# 3333.net
KiCad netlist of a schematic drawn in Altium Designer
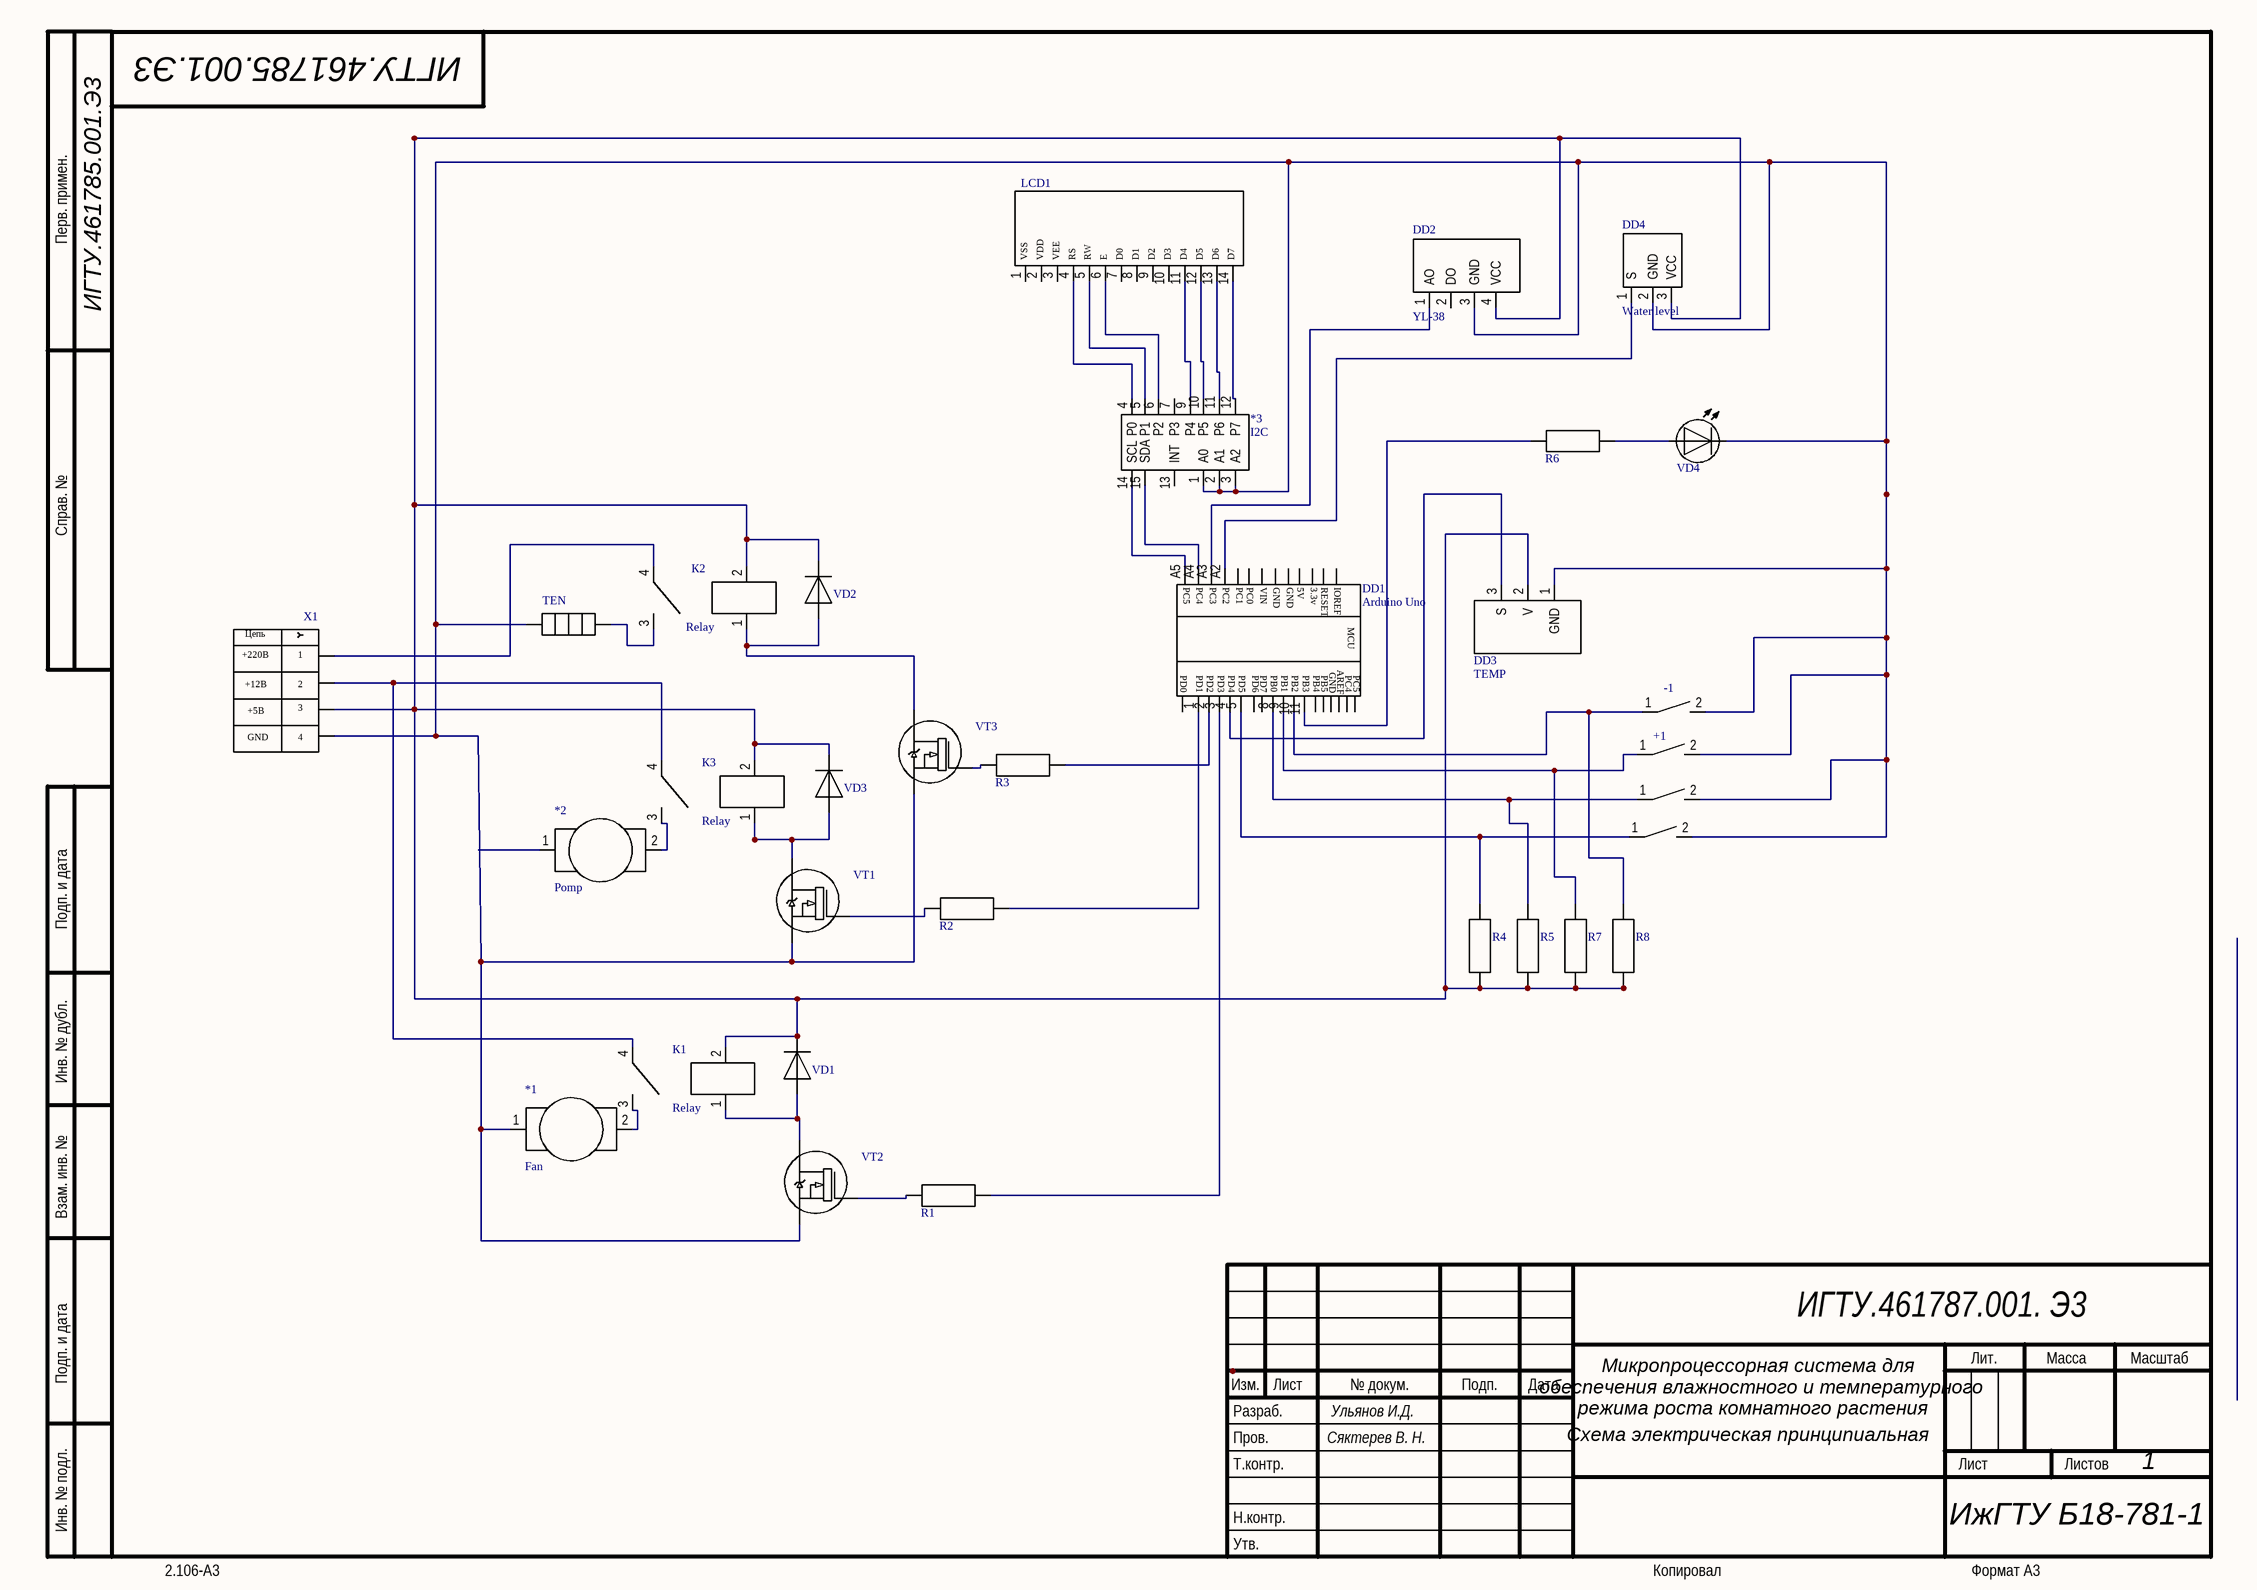
[diagram p0: Э3333.SchDoc]

(export (version "E")
  (design (tool "Eeschema 10.0.6"))
  (components
    (comp (ref "*1") (value "Fan") (libsource (lib "Schlib1") (part "Fan")))
    (comp (ref "*2")
      (value "Pomp")
      (footprint "Connector_Clapan")
      (description "помпа")
      (libsource (lib "Schlib1") (part "Pomp"))
    )
    (comp (ref "*3") (value "I2C") (libsource (lib "Schlib1") (part "I2C")))
    (comp (ref "*4")
      (value "Button")
      (footprint "button")
      (description "Кнопка")
      (libsource (lib "Schlib1") (part "Switch"))
    )
    (comp (ref "+1")
      (value "Button")
      (footprint "button")
      (description "Кнопка")
      (libsource (lib "Schlib1") (part "Switch"))
    )
    (comp (ref "-1")
      (value "Button")
      (footprint "button")
      (description "Кнопка")
      (libsource (lib "Schlib1") (part "Switch"))
    )
    (comp (ref "1")
      (value "Button")
      (footprint "button")
      (description "Кнопка")
      (libsource (lib "Schlib1") (part "Switch"))
    )
    (comp (ref "DD1")
      (value "Arduino Uno")
      (footprint "Arduino Uno")
      (description "Микроконтроллер")
      (libsource (lib "Schlib1") (part "MC"))
    )
    (comp (ref "DD2") (value "YL-38") (description "Soil m") (libsource (lib "Schlib1") (part "YL-38")))
    (comp (ref "DD3")
      (value "TEMP")
      (footprint "Connector_temp")
      (description "Терм")
      (libsource (lib "Schlib1") (part "DHT11"))
    )
    (comp (ref "DD4")
      (value "Water level")
      (footprint "Connector_Level")
      (description "Уровень воды")
      (libsource (lib "Schlib1") (part "Water lever"))
    )
    (comp (ref "LCD1")
      (value "LCD-DPY")
      (footprint "LCD")
      (description "LCD-дисплей")
      (libsource (lib "Schlib1") (part "LCD"))
    )
    (comp (ref "R1")
      (value "Resistor")
      (footprint "Resistor")
      (description "Резистор")
      (libsource (lib "Schlib1") (part "Resistor"))
    )
    (comp (ref "R2")
      (value "Resistor")
      (footprint "Resistor")
      (description "Резистор")
      (libsource (lib "Schlib1") (part "Resistor"))
    )
    (comp (ref "R3")
      (value "Resistor")
      (footprint "Resistor")
      (description "Резистор")
      (libsource (lib "Schlib1") (part "Resistor"))
    )
    (comp (ref "R4")
      (value "Resistor")
      (footprint "Resistor")
      (description "Резистор")
      (libsource (lib "Schlib1") (part "Resistor"))
    )
    (comp (ref "R5")
      (value "Resistor")
      (footprint "Resistor")
      (description "Резистор")
      (libsource (lib "Schlib1") (part "Resistor"))
    )
    (comp (ref "R6")
      (value "Resistor")
      (footprint "Resistor")
      (description "Резистор")
      (libsource (lib "Schlib1") (part "Resistor"))
    )
    (comp (ref "R7")
      (value "Resistor")
      (footprint "Resistor")
      (description "Резистор")
      (libsource (lib "Schlib1") (part "Resistor"))
    )
    (comp (ref "R8")
      (value "Resistor")
      (footprint "Resistor")
      (description "Резистор")
      (libsource (lib "Schlib1") (part "Resistor"))
    )
    (comp (ref "TEN1")
      (value "TEN")
      (footprint "Connector_TEN")
      (description "ТЭН")
      (libsource (lib "Schlib1") (part "ТЭН"))
    )
    (comp (ref "VD1")
      (value "Diode")
      (footprint "Diode")
      (description "Диод")
      (libsource (lib "Schlib1") (part "Diode"))
    )
    (comp (ref "VD2")
      (value "Diode")
      (footprint "Diode")
      (description "Диод")
      (libsource (lib "Schlib1") (part "Diode"))
    )
    (comp (ref "VD3")
      (value "Diode")
      (footprint "Diode")
      (description "Диод")
      (libsource (lib "Schlib1") (part "Diode"))
    )
    (comp (ref "VD4")
      (value "LightDiode")
      (footprint "LightDiode")
      (description "Светодиод")
      (libsource (lib "Schlib1") (part "LightDiode"))
    )
    (comp (ref "VT1")
      (value "Transistor")
      (footprint "Transistor")
      (description "Транзистор")
      (libsource (lib "Schlib1") (part "Transistor"))
    )
    (comp (ref "VT2")
      (value "Transistor")
      (footprint "Transistor")
      (description "Транзистор")
      (libsource (lib "Schlib1") (part "Transistor"))
    )
    (comp (ref "VT3")
      (value "Transistor")
      (footprint "Transistor")
      (description "Транзистор")
      (libsource (lib "Schlib1") (part "Transistor"))
    )
    (comp (ref "X1")
      (value "КД105")
      (footprint "PLS2-40")
      (description "Разъем")
      (libsource (lib "Schlib1") (part "Connector"))
    )
    (comp (ref "К1")
      (value "Relay")
      (footprint "Relay")
      (description "Реле")
      (libsource (lib "Schlib1") (part "Relay"))
    )
    (comp (ref "К2")
      (value "Relay")
      (footprint "Relay")
      (description "Реле")
      (libsource (lib "Schlib1") (part "Relay"))
    )
    (comp (ref "К3")
      (value "Relay")
      (footprint "Relay")
      (description "Реле")
      (libsource (lib "Schlib1") (part "Relay"))
    )
  )
  (nets
    (net (code "1") (name "+5В") (class "Default")
      (node (ref "DD1") (pin "5") (pinfunction "5_5") (pintype "passive"))
    )
    (net (code "2") (name "GND") (class "Default")
      (node (ref "DD1") (pin "6") (pinfunction "6_6") (pintype "passive"))
    )
    (net (code "3") (name "Net-(*1-Pad2)") (class "Default")
      (node (ref "*1") (pin "2") (pinfunction "2_2") (pintype "passive"))
      (node (ref "К1") (pin "3") (pinfunction "3_3") (pintype "passive"))
    )
    (net (code "4") (name "Net-(*2-Pad2)") (class "Default")
      (node (ref "*2") (pin "2") (pinfunction "2_2") (pintype "passive"))
      (node (ref "К3") (pin "3") (pinfunction "3_3") (pintype "passive"))
    )
    (net (code "5") (name "Net-(*3-A0)") (class "Default")
      (node (ref "*1") (pin "1") (pinfunction "1_1") (pintype "passive"))
      (node (ref "*3") (pin "1") (pinfunction "A0_1") (pintype "passive"))
      (node (ref "*3") (pin "2") (pinfunction "A1_2") (pintype "passive"))
      (node (ref "*3") (pin "3") (pinfunction "A2_3") (pintype "passive"))
      (node (ref "*4") (pin "2") (pinfunction "2_2") (pintype "passive"))
      (node (ref "+1") (pin "2") (pinfunction "2_2") (pintype "passive"))
      (node (ref "-1") (pin "2") (pinfunction "2_2") (pintype "passive"))
      (node (ref "1") (pin "2") (pinfunction "2_2") (pintype "passive"))
      (node (ref "DD2") (pin "3") (pinfunction "GND_3") (pintype "passive"))
      (node (ref "DD3") (pin "1") (pinfunction "GND_1") (pintype "passive"))
      (node (ref "DD4") (pin "2") (pinfunction "GND_2") (pintype "passive"))
      (node (ref "TEN1") (pin "1") (pinfunction "1_1") (pintype "passive"))
      (node (ref "VD4") (pin "2") (pinfunction "2_2") (pintype "passive"))
      (node (ref "VT1") (pin "2") (pinfunction "К_2") (pintype "passive"))
      (node (ref "VT2") (pin "2") (pinfunction "К_2") (pintype "passive"))
      (node (ref "VT3") (pin "2") (pinfunction "К_2") (pintype "passive"))
      (node (ref "X1") (pin "GND") (pinfunction "4_GND") (pintype "passive"))
    )
    (net (code "6") (name "Net-(*3-P0)") (class "Default")
      (node (ref "*3") (pin "4") (pinfunction "P0_4") (pintype "passive"))
      (node (ref "LCD1") (pin "4") (pinfunction "4_4") (pintype "passive"))
    )
    (net (code "7") (name "Net-(*3-P1)") (class "Default")
      (node (ref "*3") (pin "5") (pinfunction "P1_5") (pintype "passive"))
      (node (ref "LCD1") (pin "5") (pinfunction "5_5") (pintype "passive"))
    )
    (net (code "8") (name "Net-(*3-P2)") (class "Default")
      (node (ref "*3") (pin "6") (pinfunction "P2_6") (pintype "passive"))
      (node (ref "LCD1") (pin "6") (pinfunction "6_6") (pintype "passive"))
    )
    (net (code "9") (name "Net-(*3-P4)") (class "Default")
      (node (ref "*3") (pin "9") (pinfunction "P4_9") (pintype "passive"))
      (node (ref "LCD1") (pin "11") (pinfunction "11_11") (pintype "passive"))
    )
    (net (code "10") (name "Net-(*3-P5)") (class "Default")
      (node (ref "*3") (pin "10") (pinfunction "P5_10") (pintype "passive"))
      (node (ref "LCD1") (pin "12") (pinfunction "12_12") (pintype "passive"))
    )
    (net (code "11") (name "Net-(*3-P6)") (class "Default")
      (node (ref "*3") (pin "11") (pinfunction "P6_11") (pintype "passive"))
      (node (ref "LCD1") (pin "13") (pinfunction "13_13") (pintype "passive"))
    )
    (net (code "12") (name "Net-(*3-P7)") (class "Default")
      (node (ref "*3") (pin "12") (pinfunction "P7_12") (pintype "passive"))
      (node (ref "LCD1") (pin "14") (pinfunction "14_14") (pintype "passive"))
    )
    (net (code "13") (name "Net-(*3-SCL)") (class "Default")
      (node (ref "*3") (pin "14") (pinfunction "SCL_14") (pintype "passive"))
      (node (ref "DD1") (pin "A5") (pinfunction "13_A5") (pintype "passive"))
    )
    (net (code "14") (name "Net-(*3-SDA)") (class "Default")
      (node (ref "*3") (pin "15") (pinfunction "SDA_15") (pintype "passive"))
      (node (ref "DD1") (pin "A4") (pinfunction "12_A4") (pintype "passive"))
    )
    (net (code "15") (name "Net-(DD1-7)") (class "Default")
      (node (ref "DD1") (pin "2") (pinfunction "7_2") (pintype "passive"))
      (node (ref "R3") (pin "2") (pinfunction "2_2") (pintype "passive"))
    )
    (net (code "16") (name "Net-(DD1-8-Pad3)") (class "Default")
      (node (ref "DD1") (pin "3") (pinfunction "8_3") (pintype "passive"))
      (node (ref "R1") (pin "2") (pinfunction "2_2") (pintype "passive"))
    )
    (net (code "17") (name "Net-(DD1-10)") (class "Default")
      (node (ref "DD1") (pin "A2") (pinfunction "10_A2") (pintype "passive"))
      (node (ref "DD4") (pin "1") (pinfunction "S_1") (pintype "passive"))
    )
    (net (code "18") (name "Net-(DD1-11)") (class "Default")
      (node (ref "DD1") (pin "A3") (pinfunction "11_A3") (pintype "passive"))
      (node (ref "DD2") (pin "1") (pinfunction "AO_1") (pintype "passive"))
    )
    (net (code "19") (name "Net-(DD1-19)") (class "Default")
      (node (ref "+1") (pin "1") (pinfunction "1_1") (pintype "passive"))
      (node (ref "DD1") (pin "9") (pinfunction "19_9") (pintype "passive"))
      (node (ref "R7") (pin "2") (pinfunction "2_2") (pintype "passive"))
    )
    (net (code "20") (name "Net-(DD1-20)") (class "Default")
      (node (ref "1") (pin "1") (pinfunction "1_1") (pintype "passive"))
      (node (ref "DD1") (pin "8") (pinfunction "20_8") (pintype "passive"))
      (node (ref "R5") (pin "2") (pinfunction "2_2") (pintype "passive"))
    )
    (net (code "21") (name "Net-(DD1-23)") (class "Default")
      (node (ref "*4") (pin "1") (pinfunction "1_1") (pintype "passive"))
      (node (ref "DD1") (pin "5") (pinfunction "23_5") (pintype "passive"))
      (node (ref "R4") (pin "2") (pinfunction "2_2") (pintype "passive"))
    )
    (net (code "22") (name "Net-(DD1-29)") (class "Default")
      (node (ref "DD1") (pin "1") (pinfunction "29_1") (pintype "passive"))
      (node (ref "R2") (pin "2") (pinfunction "2_2") (pintype "passive"))
    )
    (net (code "23") (name "Net-(DD1-30)") (class "Default")
      (node (ref "-1") (pin "1") (pinfunction "1_1") (pintype "passive"))
      (node (ref "DD1") (pin "10") (pinfunction "30_10") (pintype "passive"))
      (node (ref "R8") (pin "2") (pinfunction "2_2") (pintype "passive"))
    )
    (net (code "24") (name "Net-(DD1-31)") (class "Default")
      (node (ref "DD1") (pin "11") (pinfunction "31_11") (pintype "passive"))
      (node (ref "R6") (pin "1") (pinfunction "1_1") (pintype "passive"))
    )
    (net (code "25") (name "Net-(DD2-VCC)") (class "Default")
      (node (ref "DD2") (pin "4") (pinfunction "VCC_4") (pintype "passive"))
      (node (ref "DD3") (pin "2") (pinfunction "V_2") (pintype "passive"))
      (node (ref "DD4") (pin "3") (pinfunction "VCC_3") (pintype "passive"))
      (node (ref "R4") (pin "1") (pinfunction "1_1") (pintype "passive"))
      (node (ref "R5") (pin "1") (pinfunction "1_1") (pintype "passive"))
      (node (ref "R7") (pin "1") (pinfunction "1_1") (pintype "passive"))
      (node (ref "R8") (pin "1") (pinfunction "1_1") (pintype "passive"))
      (node (ref "VD1") (pin "2") (pinfunction "2_2") (pintype "passive"))
      (node (ref "VD2") (pin "2") (pinfunction "2_2") (pintype "passive"))
      (node (ref "VD3") (pin "2") (pinfunction "2_2") (pintype "passive"))
      (node (ref "X1") (pin "+5В") (pinfunction "3_+5В") (pintype "passive"))
      (node (ref "К1") (pin "2") (pinfunction "2_2") (pintype "passive"))
      (node (ref "К2") (pin "2") (pinfunction "2_2") (pintype "passive"))
      (node (ref "К3") (pin "2") (pinfunction "2_2") (pintype "passive"))
    )
    (net (code "26") (name "Net-(DD3-S)") (class "Default")
      (node (ref "DD1") (pin "4") (pinfunction "8_4") (pintype "passive"))
      (node (ref "DD3") (pin "3") (pinfunction "S_3") (pintype "passive"))
    )
    (net (code "27") (name "Net-(R6-Pad2)") (class "Default")
      (node (ref "R6") (pin "2") (pinfunction "2_2") (pintype "passive"))
      (node (ref "VD4") (pin "1") (pinfunction "1_1") (pintype "passive"))
    )
    (net (code "28") (name "Net-(TEN1-Pad2)") (class "Default")
      (node (ref "TEN1") (pin "2") (pinfunction "2_2") (pintype "passive"))
      (node (ref "К2") (pin "3") (pinfunction "3_3") (pintype "passive"))
    )
    (net (code "29") (name "Net-(VT1-Б)") (class "Default")
      (node (ref "R2") (pin "1") (pinfunction "1_1") (pintype "passive"))
      (node (ref "VT1") (pin "1") (pinfunction "Б_1") (pintype "passive"))
    )
    (net (code "30") (name "Net-(VT1-Э)") (class "Default")
      (node (ref "VD3") (pin "1") (pinfunction "1_1") (pintype "passive"))
      (node (ref "VT1") (pin "3") (pinfunction "Э_3") (pintype "passive"))
      (node (ref "К3") (pin "1") (pinfunction "1_1") (pintype "passive"))
    )
    (net (code "31") (name "Net-(VT2-Б)") (class "Default")
      (node (ref "R1") (pin "1") (pinfunction "1_1") (pintype "passive"))
      (node (ref "VT2") (pin "1") (pinfunction "Б_1") (pintype "passive"))
    )
    (net (code "32") (name "Net-(VT2-Э)") (class "Default")
      (node (ref "VD1") (pin "1") (pinfunction "1_1") (pintype "passive"))
      (node (ref "VT2") (pin "3") (pinfunction "Э_3") (pintype "passive"))
      (node (ref "К1") (pin "1") (pinfunction "1_1") (pintype "passive"))
    )
    (net (code "33") (name "Net-(VT3-Б)") (class "Default")
      (node (ref "R3") (pin "1") (pinfunction "1_1") (pintype "passive"))
      (node (ref "VT3") (pin "1") (pinfunction "Б_1") (pintype "passive"))
    )
    (net (code "34") (name "Net-(VT3-Э)") (class "Default")
      (node (ref "VD2") (pin "1") (pinfunction "1_1") (pintype "passive"))
      (node (ref "VT3") (pin "3") (pinfunction "Э_3") (pintype "passive"))
      (node (ref "К2") (pin "1") (pinfunction "1_1") (pintype "passive"))
    )
    (net (code "35") (name "Net-(X1-Pad1)") (class "Default")
      (node (ref "X1") (pin "1") (pinfunction "1_1") (pintype "passive"))
      (node (ref "К2") (pin "4") (pinfunction "4_4") (pintype "passive"))
    )
    (net (code "36") (name "Net-(X1-Pad2)") (class "Default")
      (node (ref "X1") (pin "2") (pinfunction "2_2") (pintype "passive"))
      (node (ref "К1") (pin "4") (pinfunction "4_4") (pintype "passive"))
      (node (ref "К3") (pin "4") (pinfunction "4_4") (pintype "passive"))
    )
    (net (code "37") (name "unconnected-(*2-Pad1)") (class "Default")
      (node (ref "*2") (pin "1") (pinfunction "1_1") (pintype "passive"))
    )
    (net (code "38") (name "unconnected-(*3-INT-Pad13)") (class "Default")
      (node (ref "*3") (pin "13") (pinfunction "INT_13") (pintype "passive"))
    )
    (net (code "39") (name "unconnected-(*3-P3-Pad7)") (class "Default")
      (node (ref "*3") (pin "7") (pinfunction "P3_7") (pintype "passive"))
    )
    (net (code "40") (name "unconnected-(DD1-Pad1)") (class "Default")
      (node (ref "DD1") (pin "1") (pinfunction "1_1") (pintype "passive"))
    )
    (net (code "41") (name "unconnected-(DD1-Pad2)") (class "Default")
      (node (ref "DD1") (pin "2") (pinfunction "2_2") (pintype "passive"))
    )
    (net (code "42") (name "unconnected-(DD1-Pad3)") (class "Default")
      (node (ref "DD1") (pin "3") (pinfunction "3_3") (pintype "passive"))
    )
    (net (code "43") (name "unconnected-(DD1-Pad9)") (class "Default")
      (node (ref "DD1") (pin "9") (pinfunction "9_9") (pintype "passive"))
    )
    (net (code "44") (name "unconnected-(DD1-Pad21)") (class "Default")
      (node (ref "DD1") (pin "21") (pinfunction "21_21") (pintype "passive"))
    )
    (net (code "45") (name "unconnected-(DD1-Pad22)") (class "Default")
      (node (ref "DD1") (pin "22") (pinfunction "22_22") (pintype "passive"))
    )
    (net (code "46") (name "unconnected-(DD1-Pad27)") (class "Default")
      (node (ref "DD1") (pin "27") (pinfunction "27_27") (pintype "passive"))
    )
    (net (code "47") (name "unconnected-(DD1-Pad32)") (class "Default")
      (node (ref "DD1") (pin "32") (pinfunction "32_32") (pintype "passive"))
    )
    (net (code "48") (name "unconnected-(DD1-Pad33)") (class "Default")
      (node (ref "DD1") (pin "33") (pinfunction "33_33") (pintype "passive"))
    )
    (net (code "49") (name "unconnected-(DD1-Pad34)") (class "Default")
      (node (ref "DD1") (pin "34") (pinfunction "34_34") (pintype "passive"))
    )
    (net (code "50") (name "unconnected-(DD1-Pad35)") (class "Default")
      (node (ref "DD1") (pin "35") (pinfunction "35_35") (pintype "passive"))
    )
    (net (code "51") (name "unconnected-(DD1-Pad36)") (class "Default")
      (node (ref "DD1") (pin "36") (pinfunction "36_36") (pintype "passive"))
    )
    (net (code "52") (name "unconnected-(DD1-Pad37)") (class "Default")
      (node (ref "DD1") (pin "37") (pinfunction "37_37") (pintype "passive"))
    )
    (net (code "53") (name "unconnected-(DD1-Pad40)") (class "Default")
      (node (ref "DD1") (pin "40") (pinfunction "40_40") (pintype "passive"))
    )
    (net (code "54") (name "unconnected-(DD1-Pad41)") (class "Default")
      (node (ref "DD1") (pin "41") (pinfunction "41_41") (pintype "passive"))
    )
    (net (code "55") (name "unconnected-(DD1-Pad42)") (class "Default")
      (node (ref "DD1") (pin "42") (pinfunction "42_42") (pintype "passive"))
    )
    (net (code "56") (name "unconnected-(DD1-Pad43)") (class "Default")
      (node (ref "DD1") (pin "43") (pinfunction "43_43") (pintype "passive"))
    )
    (net (code "57") (name "unconnected-(DD1-Pad44)") (class "Default")
      (node (ref "DD1") (pin "44") (pinfunction "44_44") (pintype "passive"))
    )
    (net (code "58") (name "unconnected-(DD2-DO-Pad2)") (class "Default")
      (node (ref "DD2") (pin "2") (pinfunction "DO_2") (pintype "passive"))
    )
    (net (code "59") (name "unconnected-(LCD1-Pad1)") (class "Default")
      (node (ref "LCD1") (pin "1") (pinfunction "1_1") (pintype "passive"))
    )
    (net (code "60") (name "unconnected-(LCD1-Pad2)") (class "Default")
      (node (ref "LCD1") (pin "2") (pinfunction "2_2") (pintype "passive"))
    )
    (net (code "61") (name "unconnected-(LCD1-Pad3)") (class "Default")
      (node (ref "LCD1") (pin "3") (pinfunction "3_3") (pintype "passive"))
    )
    (net (code "62") (name "unconnected-(LCD1-Pad7)") (class "Default")
      (node (ref "LCD1") (pin "7") (pinfunction "7_7") (pintype "passive"))
    )
    (net (code "63") (name "unconnected-(LCD1-Pad8)") (class "Default")
      (node (ref "LCD1") (pin "8") (pinfunction "8_8") (pintype "passive"))
    )
    (net (code "64") (name "unconnected-(LCD1-Pad9)") (class "Default")
      (node (ref "LCD1") (pin "9") (pinfunction "9_9") (pintype "passive"))
    )
    (net (code "65") (name "unconnected-(LCD1-Pad10)") (class "Default")
      (node (ref "LCD1") (pin "10") (pinfunction "10_10") (pintype "passive"))
    )
  )
)
